# APP_UD_Sigle_new.net
KiCad netlist of a schematic drawn in EAGLE
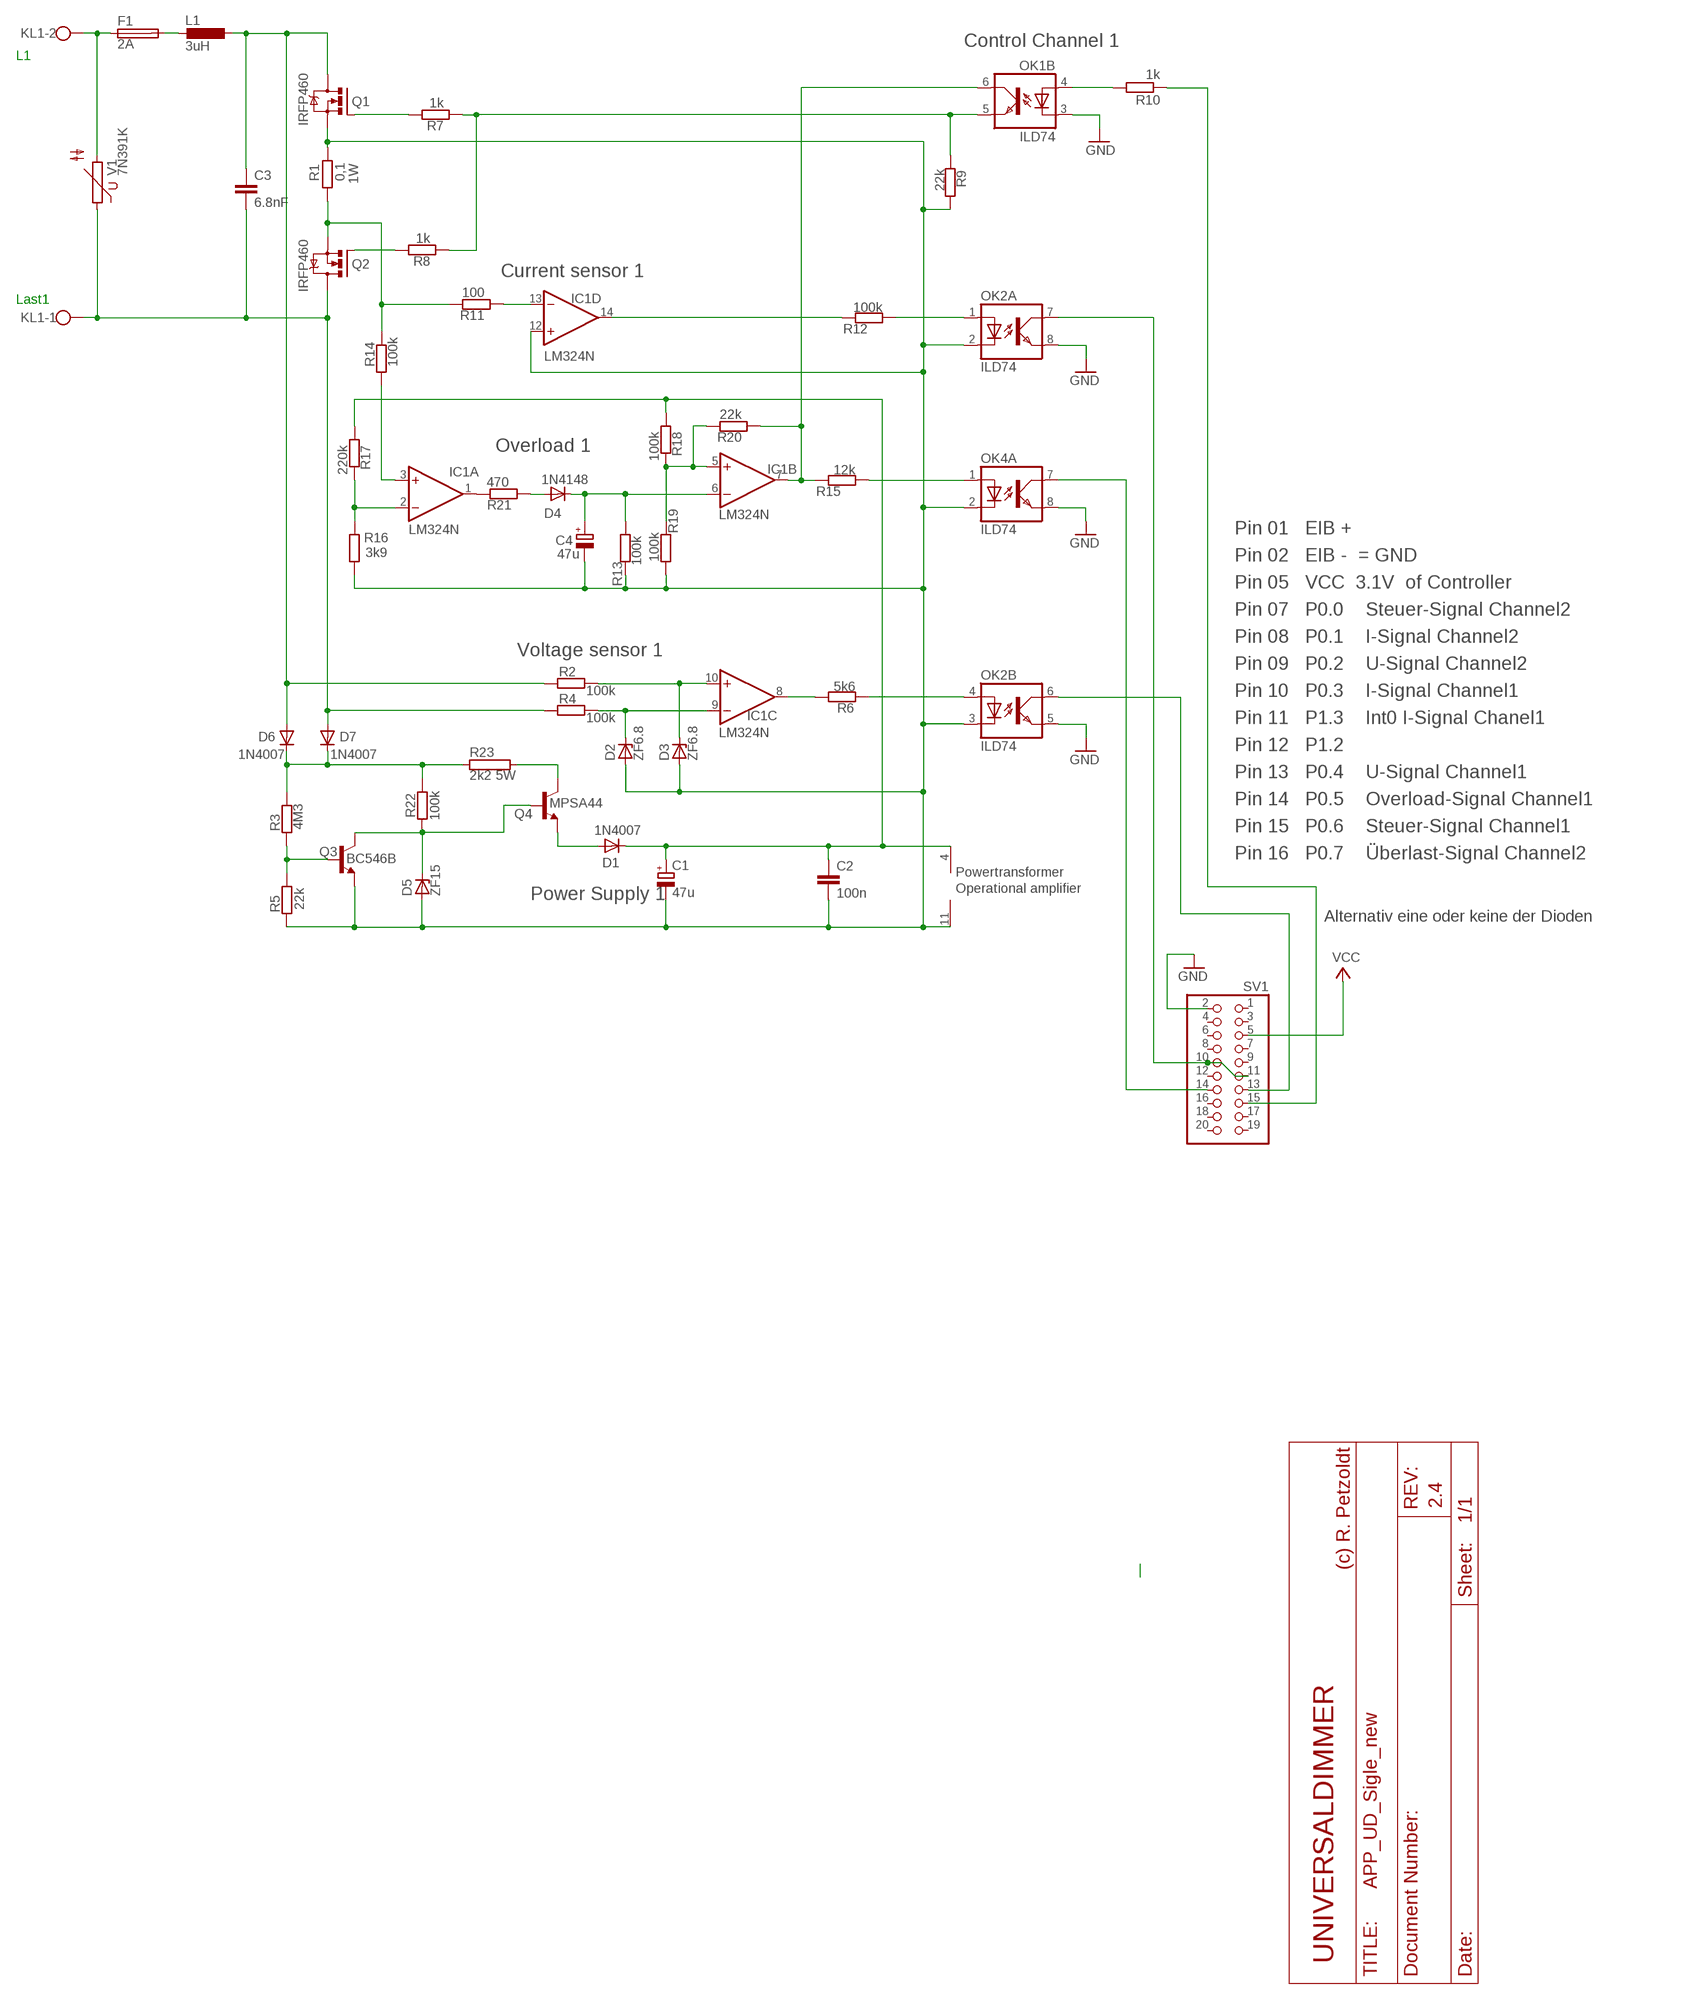
[diagram p0: schematic, sheet 1]

(export (version "E")
  (design (tool "Eeschema 10.0.6"))
  (components
    (comp (ref "C1")
      (value "47u")
      (footprint "eagle-import:E2-5")
      (libsource (lib "eagle-import") (part "CPOL-EUE2-5"))
    )
    (comp (ref "C2")
      (value "100n")
      (footprint "eagle-import:C025-030X050")
      (libsource (lib "eagle-import") (part "C-EU025-030X050"))
    )
    (comp (ref "C3")
      (value "6.8nF")
      (footprint "eagle-import:C050-075X075")
      (libsource (lib "eagle-import") (part "C-EU050-075X075"))
    )
    (comp (ref "C4")
      (value "47u")
      (footprint "eagle-import:E2-5")
      (libsource (lib "eagle-import") (part "CPOL-EUE2-5"))
    )
    (comp (ref "D1")
      (value "1N4007")
      (footprint "eagle-import:D-7")
      (libsource (lib "eagle-import") (part "1N4148DO35-7S"))
    )
    (comp (ref "D2")
      (value "ZF6.8")
      (footprint "eagle-import:ZDIO-5")
      (libsource (lib "eagle-import") (part "ZENER-DIODEZD-5"))
    )
    (comp (ref "D3")
      (value "ZF6.8")
      (footprint "eagle-import:ZDIO-7.5")
      (libsource (lib "eagle-import") (part "ZENER-DIODEZD-7.5"))
    )
    (comp (ref "D4")
      (value "1N4148")
      (footprint "eagle-import:D-7")
      (libsource (lib "eagle-import") (part "1N4148DO35-7S"))
    )
    (comp (ref "D5")
      (value "ZF15")
      (footprint "eagle-import:ZDIO-7.5")
      (libsource (lib "eagle-import") (part "ZENER-DIODEZD-7.5"))
    )
    (comp (ref "D6")
      (value "1N4007")
      (footprint "eagle-import:D-7.5")
      (libsource (lib "eagle-import") (part "DIODE-D-7.5"))
    )
    (comp (ref "D7")
      (value "1N4007")
      (footprint "eagle-import:D-7.5")
      (libsource (lib "eagle-import") (part "DIODE-D-7.5"))
    )
    (comp (ref "F1")
      (value "2A")
      (footprint "eagle-import:TR5")
      (libsource (lib "eagle-import") (part "TR5"))
    )
    (comp (ref "IC1")
      (value "LM324N")
      (footprint "eagle-import:DIL14")
      (libsource (lib "eagle-import") (part "LM324N"))
    )
    (comp (ref "KL1")
      (value "W237-102")
      (footprint "eagle-import:W237-102")
      (libsource (lib "eagle-import") (part "W237-102"))
    )
    (comp (ref "L1")
      (value "3uH")
      (footprint "eagle-import:0414V")
      (libsource (lib "eagle-import") (part "L-EU414V"))
    )
    (comp (ref "OK1")
      (value "ILD74")
      (footprint "eagle-import:DIL08")
      (libsource (lib "eagle-import") (part "ILD2"))
    )
    (comp (ref "OK2")
      (value "ILD74")
      (footprint "eagle-import:DIL08")
      (libsource (lib "eagle-import") (part "ILD2"))
    )
    (comp (ref "OK4")
      (value "ILD74")
      (footprint "eagle-import:DIL08")
      (libsource (lib "eagle-import") (part "ILD2"))
    )
    (comp (ref "Q1")
      (value "IRFP460")
      (footprint "eagle-import:TO247BV")
      (libsource (lib "eagle-import") (part "IRFPC40"))
    )
    (comp (ref "Q2")
      (value "IRFP460")
      (footprint "eagle-import:TO247BV")
      (libsource (lib "eagle-import") (part "IRFPC40"))
    )
    (comp (ref "Q3")
      (value "BC546B")
      (footprint "eagle-import:TO92-EBC")
      (libsource (lib "eagle-import") (part "BC546B"))
    )
    (comp (ref "Q4")
      (value "MPSA44")
      (footprint "eagle-import:TO92-EBC")
      (libsource (lib "eagle-import") (part "-NPN-TO92-EBCMPSA44"))
    )
    (comp (ref "R1")
      (value "0,1")
      (footprint "eagle-import:0414V")
      (libsource (lib "eagle-import") (part "R-EU_0414/5V"))
    )
    (comp (ref "R2")
      (value "100k")
      (footprint "eagle-import:0204_7")
      (libsource (lib "eagle-import") (part "R-EU_0204/7"))
    )
    (comp (ref "R3")
      (value "4M3")
      (footprint "eagle-import:0204_7")
      (libsource (lib "eagle-import") (part "R-EU_0204/7"))
    )
    (comp (ref "R4")
      (value "100k")
      (footprint "eagle-import:0204_7")
      (libsource (lib "eagle-import") (part "R-EU_0204/7"))
    )
    (comp (ref "R5")
      (value "22k")
      (footprint "eagle-import:0204_7")
      (libsource (lib "eagle-import") (part "R-EU_0204/7"))
    )
    (comp (ref "R6")
      (value "5k6")
      (footprint "eagle-import:0204_7")
      (libsource (lib "eagle-import") (part "R-EU_0204/7"))
    )
    (comp (ref "R7")
      (value "1k")
      (footprint "eagle-import:0204_7")
      (libsource (lib "eagle-import") (part "R-EU_0204/7"))
    )
    (comp (ref "R8")
      (value "1k")
      (footprint "eagle-import:0204_7")
      (libsource (lib "eagle-import") (part "R-EU_0204/7"))
    )
    (comp (ref "R9")
      (value "22k")
      (footprint "eagle-import:0204_7")
      (libsource (lib "eagle-import") (part "R-EU_0204/7"))
    )
    (comp (ref "R10")
      (value "1k")
      (footprint "eagle-import:0204_7")
      (libsource (lib "eagle-import") (part "R-EU_0204/7"))
    )
    (comp (ref "R11")
      (value "100")
      (footprint "eagle-import:0204_7")
      (libsource (lib "eagle-import") (part "R-EU_0204/7"))
    )
    (comp (ref "R12")
      (value "100k")
      (footprint "eagle-import:0204_7")
      (libsource (lib "eagle-import") (part "R-EU_0204/7"))
    )
    (comp (ref "R13")
      (value "100k")
      (footprint "eagle-import:0204_7")
      (libsource (lib "eagle-import") (part "R-EU_0204/7"))
    )
    (comp (ref "R14")
      (value "100k")
      (footprint "eagle-import:0204_7")
      (libsource (lib "eagle-import") (part "R-EU_0204/7"))
    )
    (comp (ref "R15")
      (value "12k")
      (footprint "eagle-import:0204_7")
      (libsource (lib "eagle-import") (part "R-EU_0204/7"))
    )
    (comp (ref "R16")
      (value "3k9")
      (footprint "eagle-import:0204_7")
      (libsource (lib "eagle-import") (part "R-EU_0204/7"))
    )
    (comp (ref "R17")
      (value "220k")
      (footprint "eagle-import:0204_7")
      (libsource (lib "eagle-import") (part "R-EU_0204/7"))
    )
    (comp (ref "R18")
      (value "100k")
      (footprint "eagle-import:0204_7")
      (libsource (lib "eagle-import") (part "R-EU_0204/7"))
    )
    (comp (ref "R19")
      (value "100k")
      (footprint "eagle-import:0204_7")
      (libsource (lib "eagle-import") (part "R-EU_0204/7"))
    )
    (comp (ref "R20")
      (value "22k")
      (footprint "eagle-import:0204_7")
      (libsource (lib "eagle-import") (part "R-EU_0204/7"))
    )
    (comp (ref "R21")
      (value "470")
      (footprint "eagle-import:0204_7")
      (libsource (lib "eagle-import") (part "R-EU_0204/7"))
    )
    (comp (ref "R22")
      (value "100k")
      (footprint "eagle-import:0204_7")
      (libsource (lib "eagle-import") (part "R-EU_0204/7"))
    )
    (comp (ref "R23")
      (value "2k2 5W")
      (footprint "eagle-import:KH208-8_10B")
      (libsource (lib "eagle-import") (part "R"))
    )
    (comp (ref "SV1")
      (value "PINHD-2X10")
      (footprint "eagle-import:2X10")
      (libsource (lib "eagle-import") (part "PINHD-2X10"))
    )
    (comp (ref "V1")
      (value "7N391K")
      (footprint "eagle-import:S05K11")
      (libsource (lib "eagle-import") (part "S05K11"))
    )
  )
  (nets
    (net (code "1") (name "GND") (class "Default")
      (node (ref "OK1") (pin "3") (pinfunction "C_3") (pintype "passive"))
      (node (ref "OK2") (pin "5") (pinfunction "EMIT_5") (pintype "passive"))
      (node (ref "OK2") (pin "8") (pinfunction "EMIT_8") (pintype "passive"))
      (node (ref "OK4") (pin "8") (pinfunction "EMIT_8") (pintype "passive"))
      (node (ref "SV1") (pin "2") (pinfunction "2_2") (pintype "passive"))
    )
    (net (code "2") (name "Net-(C3-Pad1)") (class "Default")
      (node (ref "C3") (pin "1") (pinfunction "1_1") (pintype "passive"))
      (node (ref "D6") (pin "A") (pinfunction "A_A") (pintype "passive"))
      (node (ref "L1") (pin "1") (pinfunction "1_1") (pintype "passive"))
      (node (ref "Q1") (pin "D") (pinfunction "D_D") (pintype "passive"))
      (node (ref "R2") (pin "1") (pinfunction "1_1") (pintype "passive"))
    )
    (net (code "3") (name "Net-(D1-PadA)") (class "Default")
      (node (ref "D1") (pin "A") (pinfunction "A_A") (pintype "passive"))
      (node (ref "Q4") (pin "E") (pinfunction "E_E") (pintype "passive"))
    )
    (net (code "4") (name "Net-(D4-PadA)") (class "Default")
      (node (ref "D4") (pin "A") (pinfunction "A_A") (pintype "passive"))
      (node (ref "R21") (pin "1") (pinfunction "1_1") (pintype "passive"))
    )
    (net (code "5") (name "Net-(D5-PadC)") (class "Default")
      (node (ref "D5") (pin "C") (pinfunction "C_C") (pintype "passive"))
      (node (ref "Q3") (pin "C") (pinfunction "C_C") (pintype "passive"))
      (node (ref "Q4") (pin "B") (pinfunction "B_B") (pintype "passive"))
      (node (ref "R22") (pin "1") (pinfunction "1_1") (pintype "passive"))
    )
    (net (code "6") (name "Net-(F1-Pad2)") (class "Default")
      (node (ref "F1") (pin "2") (pinfunction "2_2") (pintype "passive"))
      (node (ref "L1") (pin "2") (pinfunction "2_2") (pintype "passive"))
    )
    (net (code "7") (name "Net-(IC1A-+IN)") (class "Default")
      (node (ref "IC1") (pin "3") (pinfunction "+IN_3") (pintype "input"))
      (node (ref "R14") (pin "1") (pinfunction "1_1") (pintype "passive"))
    )
    (net (code "8") (name "Net-(IC1A--IN)") (class "Default")
      (node (ref "IC1") (pin "2") (pinfunction "-IN_2") (pintype "input"))
      (node (ref "R16") (pin "1") (pinfunction "1_1") (pintype "passive"))
      (node (ref "R17") (pin "2") (pinfunction "2_2") (pintype "passive"))
    )
    (net (code "9") (name "Net-(IC1A-OUT)") (class "Default")
      (node (ref "IC1") (pin "1") (pinfunction "OUT_1") (pintype "output"))
      (node (ref "R21") (pin "2") (pinfunction "2_2") (pintype "passive"))
    )
    (net (code "10") (name "Net-(IC1B-+IN)") (class "Default")
      (node (ref "IC1") (pin "5") (pinfunction "+IN_5") (pintype "input"))
      (node (ref "R18") (pin "2") (pinfunction "2_2") (pintype "passive"))
      (node (ref "R19") (pin "2") (pinfunction "2_2") (pintype "passive"))
      (node (ref "R20") (pin "2") (pinfunction "2_2") (pintype "passive"))
    )
    (net (code "11") (name "Net-(IC1B--IN)") (class "Default")
      (node (ref "C4") (pin "+") (pinfunction "+_+") (pintype "passive"))
      (node (ref "D4") (pin "C") (pinfunction "C_C") (pintype "passive"))
      (node (ref "IC1") (pin "6") (pinfunction "-IN_6") (pintype "input"))
      (node (ref "R13") (pin "1") (pinfunction "1_1") (pintype "passive"))
    )
    (net (code "12") (name "Net-(IC1B-OUT)") (class "Default")
      (node (ref "IC1") (pin "7") (pinfunction "OUT_7") (pintype "output"))
      (node (ref "OK1") (pin "6") (pinfunction "COL_6") (pintype "passive"))
      (node (ref "R15") (pin "2") (pinfunction "2_2") (pintype "passive"))
      (node (ref "R20") (pin "1") (pinfunction "1_1") (pintype "passive"))
    )
    (net (code "13") (name "Net-(IC1C-+IN)") (class "Default")
      (node (ref "D3") (pin "C") (pinfunction "C_C") (pintype "passive"))
      (node (ref "IC1") (pin "10") (pinfunction "+IN_10") (pintype "input"))
      (node (ref "R2") (pin "2") (pinfunction "2_2") (pintype "passive"))
    )
    (net (code "14") (name "Net-(IC1C--IN)") (class "Default")
      (node (ref "D2") (pin "C") (pinfunction "C_C") (pintype "passive"))
      (node (ref "IC1") (pin "9") (pinfunction "-IN_9") (pintype "input"))
      (node (ref "R4") (pin "2") (pinfunction "2_2") (pintype "passive"))
    )
    (net (code "15") (name "Net-(IC1C-OUT)") (class "Default")
      (node (ref "IC1") (pin "8") (pinfunction "OUT_8") (pintype "output"))
      (node (ref "R6") (pin "2") (pinfunction "2_2") (pintype "passive"))
    )
    (net (code "16") (name "Net-(IC1D-+IN)") (class "Default")
      (node (ref "C1") (pin "-") (pinfunction "-_-") (pintype "passive"))
      (node (ref "C2") (pin "2") (pinfunction "2_2") (pintype "passive"))
      (node (ref "C4") (pin "-") (pinfunction "-_-") (pintype "passive"))
      (node (ref "D2") (pin "A") (pinfunction "A_A") (pintype "passive"))
      (node (ref "D3") (pin "A") (pinfunction "A_A") (pintype "passive"))
      (node (ref "D5") (pin "A") (pinfunction "A_A") (pintype "passive"))
      (node (ref "IC1") (pin "11") (pinfunction "V-_11") (pintype "power_in"))
      (node (ref "IC1") (pin "12") (pinfunction "+IN_12") (pintype "input"))
      (node (ref "OK2") (pin "2") (pinfunction "C_2") (pintype "passive"))
      (node (ref "OK2") (pin "3") (pinfunction "C_3") (pintype "passive"))
      (node (ref "OK4") (pin "2") (pinfunction "C_2") (pintype "passive"))
      (node (ref "Q1") (pin "S") (pinfunction "S_S") (pintype "passive"))
      (node (ref "Q3") (pin "E") (pinfunction "E_E") (pintype "passive"))
      (node (ref "R1") (pin "2") (pinfunction "2_2") (pintype "passive"))
      (node (ref "R13") (pin "2") (pinfunction "2_2") (pintype "passive"))
      (node (ref "R16") (pin "2") (pinfunction "2_2") (pintype "passive"))
      (node (ref "R19") (pin "1") (pinfunction "1_1") (pintype "passive"))
      (node (ref "R5") (pin "1") (pinfunction "1_1") (pintype "passive"))
      (node (ref "R9") (pin "2") (pinfunction "2_2") (pintype "passive"))
    )
    (net (code "17") (name "Net-(IC1D--IN)") (class "Default")
      (node (ref "IC1") (pin "13") (pinfunction "-IN_13") (pintype "input"))
      (node (ref "R11") (pin "1") (pinfunction "1_1") (pintype "passive"))
    )
    (net (code "18") (name "Net-(IC1D-OUT)") (class "Default")
      (node (ref "IC1") (pin "14") (pinfunction "OUT_14") (pintype "output"))
      (node (ref "R12") (pin "2") (pinfunction "2_2") (pintype "passive"))
    )
    (net (code "19") (name "Net-(IC1E-V+)") (class "Default")
      (node (ref "C1") (pin "+") (pinfunction "+_+") (pintype "passive"))
      (node (ref "C2") (pin "1") (pinfunction "1_1") (pintype "passive"))
      (node (ref "D1") (pin "C") (pinfunction "C_C") (pintype "passive"))
      (node (ref "IC1") (pin "4") (pinfunction "V+_4") (pintype "power_in"))
      (node (ref "R17") (pin "1") (pinfunction "1_1") (pintype "passive"))
      (node (ref "R18") (pin "1") (pinfunction "1_1") (pintype "passive"))
    )
    (net (code "20") (name "Net-(KL1A-KL)") (class "Default")
      (node (ref "C3") (pin "2") (pinfunction "2_2") (pintype "passive"))
      (node (ref "D7") (pin "A") (pinfunction "A_A") (pintype "passive"))
      (node (ref "KL1") (pin "1") (pinfunction "KL_1") (pintype "passive"))
      (node (ref "Q2") (pin "D") (pinfunction "D_D") (pintype "passive"))
      (node (ref "R4") (pin "1") (pinfunction "1_1") (pintype "passive"))
      (node (ref "V1") (pin "1") (pinfunction "1_1") (pintype "passive"))
    )
    (net (code "21") (name "Net-(KL1B-KL)") (class "Default")
      (node (ref "F1") (pin "1") (pinfunction "1_1") (pintype "passive"))
      (node (ref "KL1") (pin "2") (pinfunction "KL_2") (pintype "passive"))
      (node (ref "V1") (pin "2") (pinfunction "2_2") (pintype "passive"))
    )
    (net (code "22") (name "Net-(OK1B-A)") (class "Default")
      (node (ref "OK1") (pin "4") (pinfunction "A_4") (pintype "passive"))
      (node (ref "R10") (pin "2") (pinfunction "2_2") (pintype "passive"))
    )
    (net (code "23") (name "Net-(OK1B-EMIT)") (class "Default")
      (node (ref "OK1") (pin "5") (pinfunction "EMIT_5") (pintype "passive"))
      (node (ref "R7") (pin "1") (pinfunction "1_1") (pintype "passive"))
      (node (ref "R8") (pin "1") (pinfunction "1_1") (pintype "passive"))
      (node (ref "R9") (pin "1") (pinfunction "1_1") (pintype "passive"))
    )
    (net (code "24") (name "Net-(OK2A-A)") (class "Default")
      (node (ref "OK2") (pin "1") (pinfunction "A_1") (pintype "passive"))
      (node (ref "R12") (pin "1") (pinfunction "1_1") (pintype "passive"))
    )
    (net (code "25") (name "Net-(OK2A-COL)") (class "Default")
      (node (ref "OK2") (pin "7") (pinfunction "COL_7") (pintype "passive"))
      (node (ref "SV1") (pin "10") (pinfunction "10_10") (pintype "passive"))
      (node (ref "SV1") (pin "11") (pinfunction "11_11") (pintype "passive"))
    )
    (net (code "26") (name "Net-(OK2B-A)") (class "Default")
      (node (ref "OK2") (pin "4") (pinfunction "A_4") (pintype "passive"))
      (node (ref "R6") (pin "1") (pinfunction "1_1") (pintype "passive"))
    )
    (net (code "27") (name "Net-(OK2B-COL)") (class "Default")
      (node (ref "OK2") (pin "6") (pinfunction "COL_6") (pintype "passive"))
      (node (ref "SV1") (pin "13") (pinfunction "13_13") (pintype "passive"))
    )
    (net (code "28") (name "Net-(OK4A-A)") (class "Default")
      (node (ref "OK4") (pin "1") (pinfunction "A_1") (pintype "passive"))
      (node (ref "R15") (pin "1") (pinfunction "1_1") (pintype "passive"))
    )
    (net (code "29") (name "Net-(OK4A-COL)") (class "Default")
      (node (ref "OK4") (pin "7") (pinfunction "COL_7") (pintype "passive"))
      (node (ref "SV1") (pin "14") (pinfunction "14_14") (pintype "passive"))
    )
    (net (code "30") (name "Net-(Q1-PadG)") (class "Default")
      (node (ref "Q1") (pin "G") (pinfunction "G_G") (pintype "passive"))
      (node (ref "R7") (pin "2") (pinfunction "2_2") (pintype "passive"))
    )
    (net (code "31") (name "Net-(Q2-PadG)") (class "Default")
      (node (ref "Q2") (pin "G") (pinfunction "G_G") (pintype "passive"))
      (node (ref "R8") (pin "2") (pinfunction "2_2") (pintype "passive"))
    )
    (net (code "32") (name "Net-(Q2-PadS)") (class "Default")
      (node (ref "Q2") (pin "S") (pinfunction "S_S") (pintype "passive"))
      (node (ref "R1") (pin "1") (pinfunction "1_1") (pintype "passive"))
      (node (ref "R11") (pin "2") (pinfunction "2_2") (pintype "passive"))
      (node (ref "R14") (pin "2") (pinfunction "2_2") (pintype "passive"))
    )
    (net (code "33") (name "Net-(Q3-PadB)") (class "Default")
      (node (ref "Q3") (pin "B") (pinfunction "B_B") (pintype "passive"))
      (node (ref "R3") (pin "1") (pinfunction "1_1") (pintype "passive"))
      (node (ref "R5") (pin "2") (pinfunction "2_2") (pintype "passive"))
    )
    (net (code "34") (name "Net-(R10-Pad1)") (class "Default")
      (node (ref "R10") (pin "1") (pinfunction "1_1") (pintype "passive"))
      (node (ref "SV1") (pin "15") (pinfunction "15_15") (pintype "passive"))
    )
    (net (code "35") (name "Net-(R23-1)") (class "Default")
      (node (ref "D6") (pin "C") (pinfunction "C_C") (pintype "passive"))
      (node (ref "D7") (pin "C") (pinfunction "C_C") (pintype "passive"))
      (node (ref "R22") (pin "2") (pinfunction "2_2") (pintype "passive"))
      (node (ref "R23") (pin "P$1") (pinfunction "1_P$1") (pintype "passive"))
      (node (ref "R3") (pin "2") (pinfunction "2_2") (pintype "passive"))
    )
    (net (code "36") (name "Net-(R23-2)") (class "Default")
      (node (ref "Q4") (pin "C") (pinfunction "C_C") (pintype "passive"))
      (node (ref "R23") (pin "P$2") (pinfunction "2_P$2") (pintype "passive"))
    )
    (net (code "37") (name "VCC") (class "Default")
      (node (ref "SV1") (pin "5") (pinfunction "5_5") (pintype "passive"))
    )
    (net (code "38") (name "unconnected-(SV1-Pad1)") (class "Default")
      (node (ref "SV1") (pin "1") (pinfunction "1_1") (pintype "passive"))
    )
    (net (code "39") (name "unconnected-(SV1-Pad3)") (class "Default")
      (node (ref "SV1") (pin "3") (pinfunction "3_3") (pintype "passive"))
    )
    (net (code "40") (name "unconnected-(SV1-Pad4)") (class "Default")
      (node (ref "SV1") (pin "4") (pinfunction "4_4") (pintype "passive"))
    )
    (net (code "41") (name "unconnected-(SV1-Pad6)") (class "Default")
      (node (ref "SV1") (pin "6") (pinfunction "6_6") (pintype "passive"))
    )
    (net (code "42") (name "unconnected-(SV1-Pad7)") (class "Default")
      (node (ref "SV1") (pin "7") (pinfunction "7_7") (pintype "passive"))
    )
    (net (code "43") (name "unconnected-(SV1-Pad8)") (class "Default")
      (node (ref "SV1") (pin "8") (pinfunction "8_8") (pintype "passive"))
    )
    (net (code "44") (name "unconnected-(SV1-Pad9)") (class "Default")
      (node (ref "SV1") (pin "9") (pinfunction "9_9") (pintype "passive"))
    )
    (net (code "45") (name "unconnected-(SV1-Pad12)") (class "Default")
      (node (ref "SV1") (pin "12") (pinfunction "12_12") (pintype "passive"))
    )
    (net (code "46") (name "unconnected-(SV1-Pad16)") (class "Default")
      (node (ref "SV1") (pin "16") (pinfunction "16_16") (pintype "passive"))
    )
    (net (code "47") (name "unconnected-(SV1-Pad17)") (class "Default")
      (node (ref "SV1") (pin "17") (pinfunction "17_17") (pintype "passive"))
    )
    (net (code "48") (name "unconnected-(SV1-Pad18)") (class "Default")
      (node (ref "SV1") (pin "18") (pinfunction "18_18") (pintype "passive"))
    )
    (net (code "49") (name "unconnected-(SV1-Pad19)") (class "Default")
      (node (ref "SV1") (pin "19") (pinfunction "19_19") (pintype "passive"))
    )
    (net (code "50") (name "unconnected-(SV1-Pad20)") (class "Default")
      (node (ref "SV1") (pin "20") (pinfunction "20_20") (pintype "passive"))
    )
  )
)
